# Digital_Inputs.net
KiCad netlist of a schematic drawn in Altium Designer
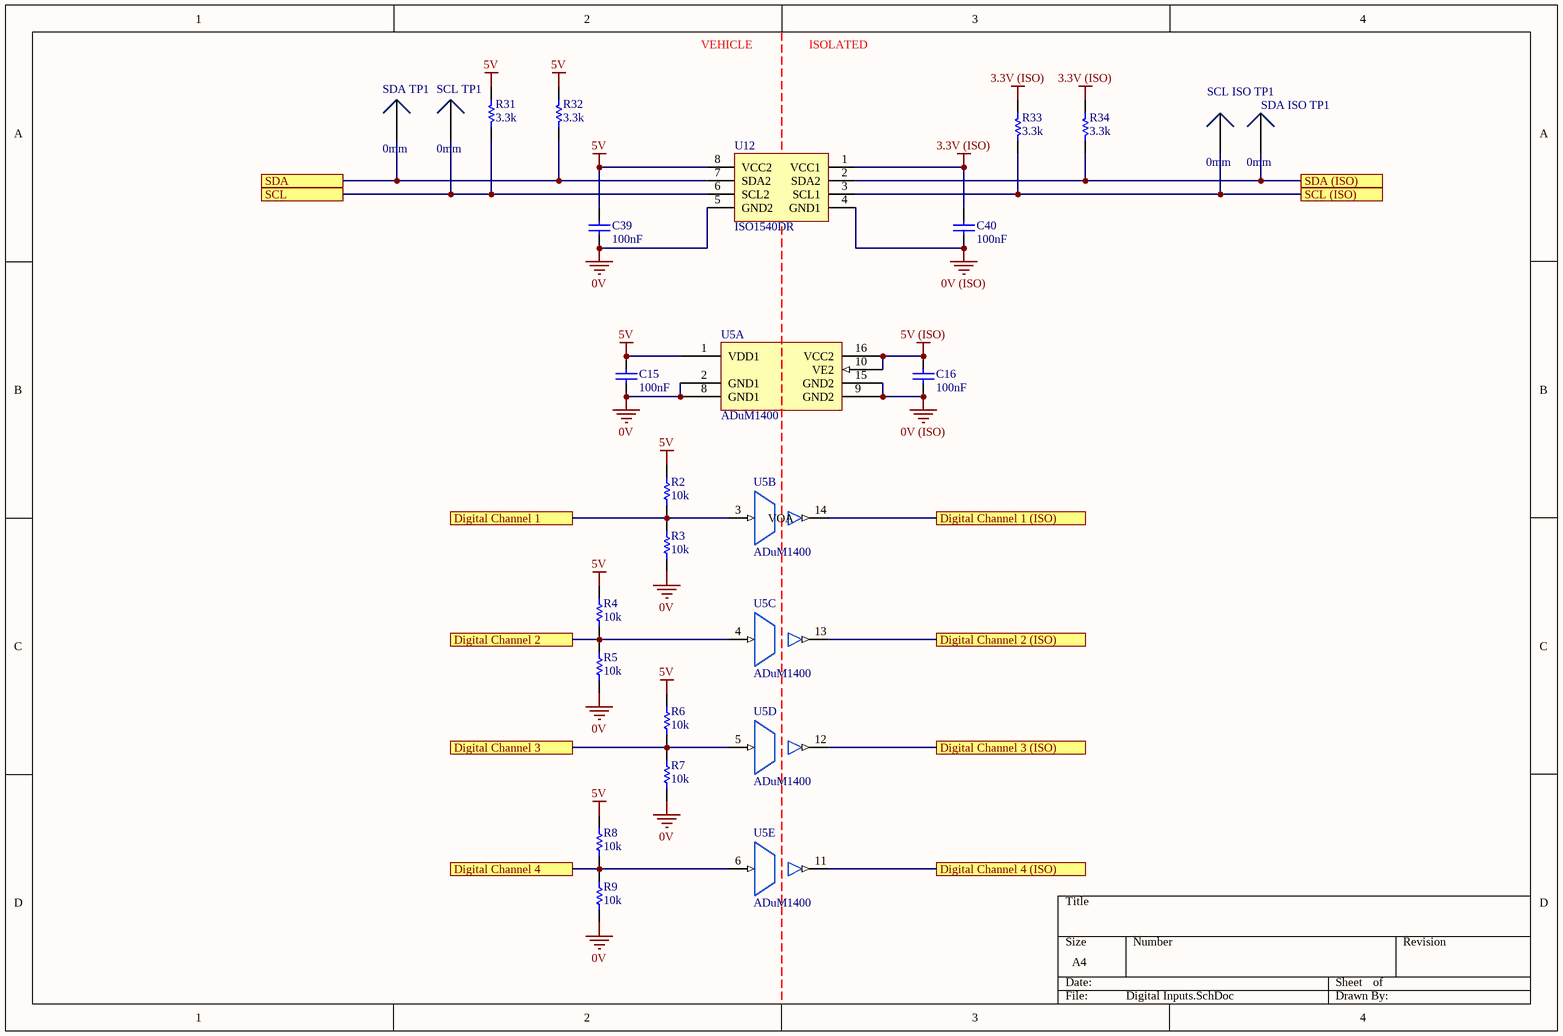
[diagram p0: Digital Inputs.SchDoc]

(export (version "E")
  (design (tool "Eeschema 10.0.6"))
  (components
    (comp (ref "C15")
      (value "100nF")
      (footprint "0805")
      (fields
        (field (name "PART NUMBER") "GCM21BR71E104KA37L")
        (field (name "TOLERANCE") "10%")
        (field (name "MANUFACTURER") "muRata")
      )
      (libsource (lib "ts_20-standard-library") (part "Capacitor"))
    )
    (comp (ref "C16")
      (value "100nF")
      (footprint "0805")
      (fields
        (field (name "PART NUMBER") "GCM21BR71E104KA37L")
        (field (name "TOLERANCE") "10%")
        (field (name "MANUFACTURER") "muRata")
      )
      (libsource (lib "ts_20-standard-library") (part "Capacitor"))
    )
    (comp (ref "C39")
      (value "100nF")
      (footprint "0805")
      (fields
        (field (name "PART NUMBER") "GCM21BR71E104KA37L")
        (field (name "TOLERANCE") "10%")
        (field (name "MANUFACTURER") "muRata")
      )
      (libsource (lib "ts_20-standard-library") (part "Capacitor"))
    )
    (comp (ref "C40")
      (value "100nF")
      (footprint "0805")
      (fields
        (field (name "PART NUMBER") "GCM21BR71E104KA37L")
        (field (name "TOLERANCE") "10%")
        (field (name "MANUFACTURER") "muRata")
      )
      (libsource (lib "ts_20-standard-library") (part "Capacitor"))
    )
    (comp (ref "R2")
      (value "10k")
      (footprint "0805")
      (fields
        (field (name "PART NUMBER") "RC0805FR0710KL")
        (field (name "MANUFACTURER") "YAGEO")
        (field (name "TOLERANCE") "0.01")
      )
      (libsource (lib "ts_20-standard-library") (part "Resistor"))
    )
    (comp (ref "R3")
      (value "10k")
      (footprint "0805")
      (fields
        (field (name "PART NUMBER") "RC0805FR0710KL")
        (field (name "MANUFACTURER") "YAGEO")
        (field (name "TOLERANCE") "0.01")
      )
      (libsource (lib "ts_20-standard-library") (part "Resistor"))
    )
    (comp (ref "R4")
      (value "10k")
      (footprint "0805")
      (fields
        (field (name "PART NUMBER") "RC0805FR0710KL")
        (field (name "MANUFACTURER") "YAGEO")
        (field (name "TOLERANCE") "0.01")
      )
      (libsource (lib "ts_20-standard-library") (part "Resistor"))
    )
    (comp (ref "R5")
      (value "10k")
      (footprint "0805")
      (fields
        (field (name "PART NUMBER") "RC0805FR0710KL")
        (field (name "MANUFACTURER") "YAGEO")
        (field (name "TOLERANCE") "0.01")
      )
      (libsource (lib "ts_20-standard-library") (part "Resistor"))
    )
    (comp (ref "R6")
      (value "10k")
      (footprint "0805")
      (fields
        (field (name "PART NUMBER") "RC0805FR0710KL")
        (field (name "MANUFACTURER") "YAGEO")
        (field (name "TOLERANCE") "0.01")
      )
      (libsource (lib "ts_20-standard-library") (part "Resistor"))
    )
    (comp (ref "R7")
      (value "10k")
      (footprint "0805")
      (fields
        (field (name "PART NUMBER") "RC0805FR0710KL")
        (field (name "MANUFACTURER") "YAGEO")
        (field (name "TOLERANCE") "0.01")
      )
      (libsource (lib "ts_20-standard-library") (part "Resistor"))
    )
    (comp (ref "R8")
      (value "10k")
      (footprint "0805")
      (fields
        (field (name "PART NUMBER") "RC0805FR0710KL")
        (field (name "MANUFACTURER") "YAGEO")
        (field (name "TOLERANCE") "0.01")
      )
      (libsource (lib "ts_20-standard-library") (part "Resistor"))
    )
    (comp (ref "R9")
      (value "10k")
      (footprint "0805")
      (fields
        (field (name "PART NUMBER") "RC0805FR0710KL")
        (field (name "MANUFACTURER") "YAGEO")
        (field (name "TOLERANCE") "0.01")
      )
      (libsource (lib "ts_20-standard-library") (part "Resistor"))
    )
    (comp (ref "R31")
      (value "3.3k")
      (footprint "0805")
      (fields
        (field (name "PART NUMBER") "RC0805FR073K3L")
        (field (name "MANUFACTURER") "YAGEO")
        (field (name "TOLERANCE") "0.01")
      )
      (libsource (lib "ts_20-standard-library") (part "Resistor"))
    )
    (comp (ref "R32")
      (value "3.3k")
      (footprint "0805")
      (fields
        (field (name "PART NUMBER") "RC0805FR073K3L")
        (field (name "MANUFACTURER") "YAGEO")
        (field (name "TOLERANCE") "0.01")
      )
      (libsource (lib "ts_20-standard-library") (part "Resistor"))
    )
    (comp (ref "R33")
      (value "3.3k")
      (footprint "0805")
      (fields
        (field (name "PART NUMBER") "RC0805FR073K3L")
        (field (name "MANUFACTURER") "YAGEO")
        (field (name "TOLERANCE") "0.01")
      )
      (libsource (lib "ts_20-standard-library") (part "Resistor"))
    )
    (comp (ref "R34")
      (value "3.3k")
      (footprint "0805")
      (fields
        (field (name "PART NUMBER") "RC0805FR073K3L")
        (field (name "MANUFACTURER") "YAGEO")
        (field (name "TOLERANCE") "0.01")
      )
      (libsource (lib "ts_20-standard-library") (part "Resistor"))
    )
    (comp (ref "SCL ISO TP1")
      (value "0mm")
      (footprint "SMD Test Point")
      (fields (field (name "PART NUMBER") "SMD Test Point") (field (name "CONTACT") "NA"))
      (libsource (lib "ts_20-standard-connectors") (part "Test Point"))
    )
    (comp (ref "SCL TP1")
      (value "0mm")
      (footprint "SMD Test Point")
      (fields (field (name "PART NUMBER") "SMD Test Point") (field (name "CONTACT") "NA"))
      (libsource (lib "ts_20-standard-connectors") (part "Test Point"))
    )
    (comp (ref "SDA ISO TP1")
      (value "0mm")
      (footprint "SMD Test Point")
      (fields (field (name "PART NUMBER") "SMD Test Point") (field (name "CONTACT") "NA"))
      (libsource (lib "ts_20-standard-connectors") (part "Test Point"))
    )
    (comp (ref "SDA TP1")
      (value "0mm")
      (footprint "SMD Test Point")
      (fields (field (name "PART NUMBER") "SMD Test Point") (field (name "CONTACT") "NA"))
      (libsource (lib "ts_20-standard-connectors") (part "Test Point"))
    )
    (comp (ref "U5")
      (value "ADuM1400")
      (footprint "AD 16-SOIC")
      (fields
        (field (name "MANUFACTURER") "Analog Devices")
        (field (name "DIGIKEY PART NUMBER") "ADUM1400WSRWZ-ND")
      )
      (libsource (lib "ts_20-standard-library") (part "ADuM1400"))
    )
    (comp (ref "U12")
      (value "ISO1540DR")
      (footprint "TI 8-SOIC")
      (description "I2C Digital Isolator (Multichannel)")
      (fields
        (field (name "MANUFACTURER") "Texas Instruments")
        (field (name "DIGIKEY PART NUMBER") "296-34871-1-ND")
      )
      (libsource (lib "ts_20-standard-library") (part "ISO1540DR"))
    )
  )
  (nets
    (net (code "1") (name "/Digital Channel 1") (class "Default")
      (node (ref "R2") (pin "1") (pinfunction "1_1") (pintype "passive"))
      (node (ref "R3") (pin "2") (pinfunction "2_2") (pintype "passive"))
      (node (ref "U5") (pin "3") (pinfunction "VIA_3") (pintype "input"))
    )
    (net (code "2") (name "/Digital Channel 1 (ISO)") (class "Default")
      (node (ref "U5") (pin "14") (pinfunction "VOA_14") (pintype "output"))
    )
    (net (code "3") (name "/Digital Channel 2") (class "Default")
      (node (ref "R4") (pin "1") (pinfunction "1_1") (pintype "passive"))
      (node (ref "R5") (pin "2") (pinfunction "2_2") (pintype "passive"))
      (node (ref "U5") (pin "4") (pinfunction "VIB_4") (pintype "input"))
    )
    (net (code "4") (name "/Digital Channel 2 (ISO)") (class "Default")
      (node (ref "U5") (pin "13") (pinfunction "VOB_13") (pintype "output"))
    )
    (net (code "5") (name "/Digital Channel 3") (class "Default")
      (node (ref "R6") (pin "1") (pinfunction "1_1") (pintype "passive"))
      (node (ref "R7") (pin "2") (pinfunction "2_2") (pintype "passive"))
      (node (ref "U5") (pin "5") (pinfunction "VIC_5") (pintype "input"))
    )
    (net (code "6") (name "/Digital Channel 3 (ISO)") (class "Default")
      (node (ref "U5") (pin "12") (pinfunction "VOC_12") (pintype "output"))
    )
    (net (code "7") (name "/Digital Channel 4") (class "Default")
      (node (ref "R8") (pin "1") (pinfunction "1_1") (pintype "passive"))
      (node (ref "R9") (pin "2") (pinfunction "2_2") (pintype "passive"))
      (node (ref "U5") (pin "6") (pinfunction "VID_6") (pintype "input"))
    )
    (net (code "8") (name "/Digital Channel 4 (ISO)") (class "Default")
      (node (ref "U5") (pin "11") (pinfunction "VOD_11") (pintype "output"))
    )
    (net (code "9") (name "/SCL") (class "Default")
      (node (ref "R31") (pin "1") (pinfunction "1_1") (pintype "passive"))
      (node (ref "SCL TP1") (pin "1") (pinfunction "1_1") (pintype "passive"))
      (node (ref "U12") (pin "6") (pinfunction "SCL2_6") (pintype "power_in"))
    )
    (net (code "10") (name "/SCL (ISO)") (class "Default")
      (node (ref "R33") (pin "1") (pinfunction "1_1") (pintype "passive"))
      (node (ref "SCL ISO TP1") (pin "1") (pinfunction "1_1") (pintype "passive"))
      (node (ref "U12") (pin "3") (pinfunction "SCL1_3") (pintype "power_in"))
    )
    (net (code "11") (name "/SDA") (class "Default")
      (node (ref "R32") (pin "1") (pinfunction "1_1") (pintype "passive"))
      (node (ref "SDA TP1") (pin "1") (pinfunction "1_1") (pintype "passive"))
      (node (ref "U12") (pin "7") (pinfunction "SDA2_7") (pintype "power_in"))
    )
    (net (code "12") (name "/SDA (ISO)") (class "Default")
      (node (ref "R34") (pin "1") (pinfunction "1_1") (pintype "passive"))
      (node (ref "SDA ISO TP1") (pin "1") (pinfunction "1_1") (pintype "passive"))
      (node (ref "U12") (pin "2") (pinfunction "SDA2_2") (pintype "power_in"))
    )
    (net (code "13") (name "0V") (class "Default")
      (node (ref "C15") (pin "1") (pinfunction "1_1") (pintype "passive"))
      (node (ref "C39") (pin "1") (pinfunction "1_1") (pintype "passive"))
      (node (ref "R3") (pin "1") (pinfunction "1_1") (pintype "passive"))
      (node (ref "R5") (pin "1") (pinfunction "1_1") (pintype "passive"))
      (node (ref "R7") (pin "1") (pinfunction "1_1") (pintype "passive"))
      (node (ref "R9") (pin "1") (pinfunction "1_1") (pintype "passive"))
      (node (ref "U12") (pin "5") (pinfunction "GND2_5") (pintype "power_in"))
      (node (ref "U5") (pin "2") (pinfunction "GND1_2") (pintype "power_in"))
      (node (ref "U5") (pin "8") (pinfunction "GND1_8") (pintype "power_in"))
    )
    (net (code "14") (name "0V (ISO)") (class "Default")
      (node (ref "C16") (pin "1") (pinfunction "1_1") (pintype "passive"))
      (node (ref "C40") (pin "1") (pinfunction "1_1") (pintype "passive"))
      (node (ref "U12") (pin "4") (pinfunction "GND1_4") (pintype "power_in"))
      (node (ref "U5") (pin "15") (pinfunction "GND2_15") (pintype "power_in"))
      (node (ref "U5") (pin "9") (pinfunction "GND2_9") (pintype "power_in"))
    )
    (net (code "15") (name "3.3V (ISO)") (class "Default")
      (node (ref "C40") (pin "2") (pinfunction "2_2") (pintype "passive"))
      (node (ref "R33") (pin "2") (pinfunction "2_2") (pintype "passive"))
      (node (ref "R34") (pin "2") (pinfunction "2_2") (pintype "passive"))
      (node (ref "U12") (pin "1") (pinfunction "VCC1_1") (pintype "power_in"))
    )
    (net (code "16") (name "5V") (class "Default")
      (node (ref "C15") (pin "2") (pinfunction "2_2") (pintype "passive"))
      (node (ref "C39") (pin "2") (pinfunction "2_2") (pintype "passive"))
      (node (ref "R2") (pin "2") (pinfunction "2_2") (pintype "passive"))
      (node (ref "R31") (pin "2") (pinfunction "2_2") (pintype "passive"))
      (node (ref "R32") (pin "2") (pinfunction "2_2") (pintype "passive"))
      (node (ref "R4") (pin "2") (pinfunction "2_2") (pintype "passive"))
      (node (ref "R6") (pin "2") (pinfunction "2_2") (pintype "passive"))
      (node (ref "R8") (pin "2") (pinfunction "2_2") (pintype "passive"))
      (node (ref "U12") (pin "8") (pinfunction "VCC2_8") (pintype "power_in"))
      (node (ref "U5") (pin "1") (pinfunction "VDD1_1") (pintype "power_in"))
    )
    (net (code "17") (name "5V (ISO)") (class "Default")
      (node (ref "C16") (pin "2") (pinfunction "2_2") (pintype "passive"))
      (node (ref "U5") (pin "10") (pinfunction "VE2_10") (pintype "input"))
      (node (ref "U5") (pin "16") (pinfunction "VCC2_16") (pintype "power_in"))
    )
  )
)
